# PiezoMini.net
KiCad netlist of a schematic drawn in EAGLE
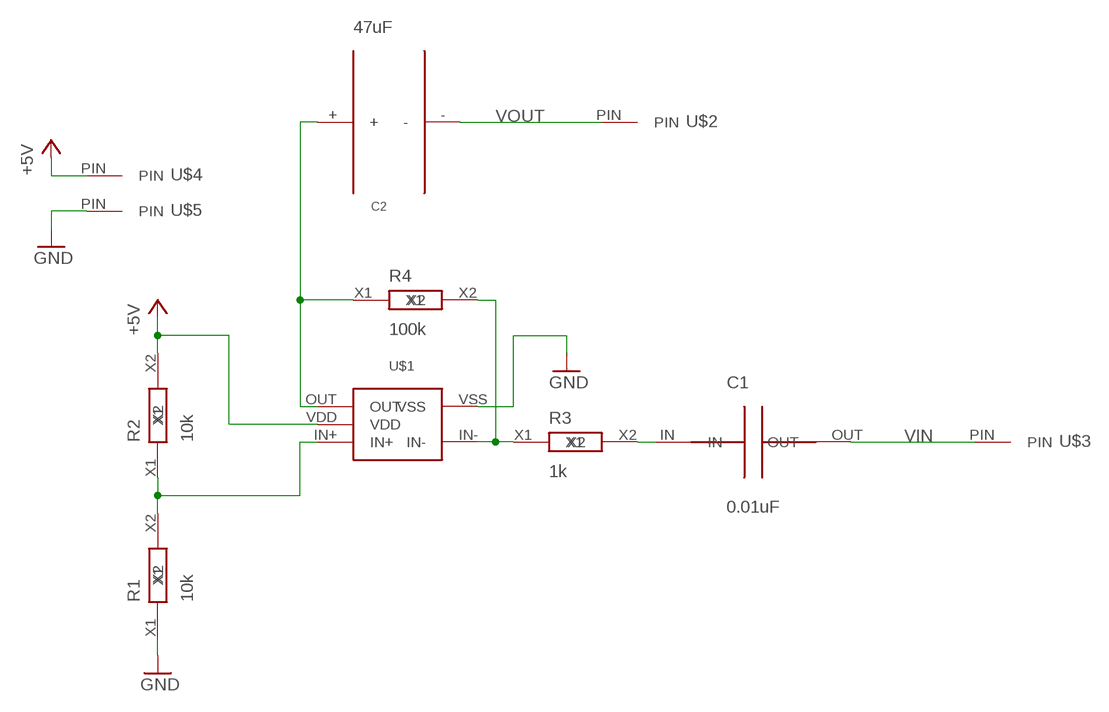
[diagram p0: schematic, sheet 1]

(export (version "E")
  (design (tool "Eeschema 10.0.6"))
  (components
    (comp (ref "C1")
      (value "0.01uF")
      (footprint "eagle-import:C_CER_5MM")
      (libsource (lib "eagle-import") (part "C_CER_5MM"))
    )
    (comp (ref "C2")
      (value "47uF")
      (footprint "eagle-import:C100UF")
      (libsource (lib "eagle-import") (part "C100UF"))
    )
    (comp (ref "R1")
      (value "10k")
      (footprint "eagle-import:SMD_2.1X1.25")
      (libsource (lib "eagle-import") (part "R_SMD_2.1X1.25"))
    )
    (comp (ref "R2")
      (value "10k")
      (footprint "eagle-import:SMD_2.1X1.25")
      (libsource (lib "eagle-import") (part "R_SMD_2.1X1.25"))
    )
    (comp (ref "R3")
      (value "1k")
      (footprint "eagle-import:SMD_2.1X1.25")
      (libsource (lib "eagle-import") (part "R_SMD_2.1X1.25"))
    )
    (comp (ref "R4")
      (value "100k")
      (footprint "eagle-import:SMD_2.1X1.25")
      (libsource (lib "eagle-import") (part "R_SMD_2.1X1.25"))
    )
    (comp (ref "U$1")
      (value "MCP6L91")
      (footprint "eagle-import:MCP6L91")
      (libsource (lib "eagle-import") (part "MCP6L91"))
    )
    (comp (ref "U$2")
      (value "PIN")
      (footprint "eagle-import:PIN")
      (libsource (lib "eagle-import") (part "PIN"))
    )
    (comp (ref "U$3")
      (value "PIN")
      (footprint "eagle-import:PIN")
      (libsource (lib "eagle-import") (part "PIN"))
    )
    (comp (ref "U$4")
      (value "PIN")
      (footprint "eagle-import:PIN")
      (libsource (lib "eagle-import") (part "PIN"))
    )
    (comp (ref "U$5")
      (value "PIN")
      (footprint "eagle-import:PIN")
      (libsource (lib "eagle-import") (part "PIN"))
    )
  )
  (nets
    (net (code "1") (name "+5V") (class "Default")
      (node (ref "R2") (pin "X2") (pinfunction "X2_X2") (pintype "bidirectional"))
      (node (ref "U$1") (pin "VDD") (pinfunction "VDD_VDD") (pintype "bidirectional"))
      (node (ref "U$4") (pin "PIN") (pinfunction "PIN_PIN") (pintype "bidirectional"))
    )
    (net (code "2") (name "/VIN") (class "Default")
      (node (ref "C1") (pin "OUT") (pinfunction "OUT_OUT") (pintype "bidirectional"))
      (node (ref "U$3") (pin "PIN") (pinfunction "PIN_PIN") (pintype "bidirectional"))
    )
    (net (code "3") (name "/VOUT") (class "Default")
      (node (ref "C2") (pin "-") (pinfunction "-_-") (pintype "bidirectional"))
      (node (ref "U$2") (pin "PIN") (pinfunction "PIN_PIN") (pintype "bidirectional"))
    )
    (net (code "4") (name "GND") (class "Default")
      (node (ref "R1") (pin "X1") (pinfunction "X1_X1") (pintype "bidirectional"))
      (node (ref "U$1") (pin "VSS") (pinfunction "VSS_VSS") (pintype "bidirectional"))
      (node (ref "U$5") (pin "PIN") (pinfunction "PIN_PIN") (pintype "bidirectional"))
    )
    (net (code "5") (name "Net-(C1-PadIN)") (class "Default")
      (node (ref "C1") (pin "IN") (pinfunction "IN_IN") (pintype "bidirectional"))
      (node (ref "R3") (pin "X2") (pinfunction "X2_X2") (pintype "bidirectional"))
    )
    (net (code "6") (name "Net-(C2-Pad+)") (class "Default")
      (node (ref "C2") (pin "+") (pinfunction "+_+") (pintype "bidirectional"))
      (node (ref "R4") (pin "X1") (pinfunction "X1_X1") (pintype "bidirectional"))
      (node (ref "U$1") (pin "OUT") (pinfunction "OUT_OUT") (pintype "bidirectional"))
    )
    (net (code "7") (name "Net-(R1-PadX2)") (class "Default")
      (node (ref "R1") (pin "X2") (pinfunction "X2_X2") (pintype "bidirectional"))
      (node (ref "R2") (pin "X1") (pinfunction "X1_X1") (pintype "bidirectional"))
      (node (ref "U$1") (pin "IN+") (pinfunction "IN+_IN+") (pintype "bidirectional"))
    )
    (net (code "8") (name "Net-(R3-PadX1)") (class "Default")
      (node (ref "R3") (pin "X1") (pinfunction "X1_X1") (pintype "bidirectional"))
      (node (ref "R4") (pin "X2") (pinfunction "X2_X2") (pintype "bidirectional"))
      (node (ref "U$1") (pin "IN-") (pinfunction "IN-_IN-") (pintype "bidirectional"))
    )
  )
)
